# MCU_STM32.net
KiCad netlist of a schematic drawn in Altium Designer
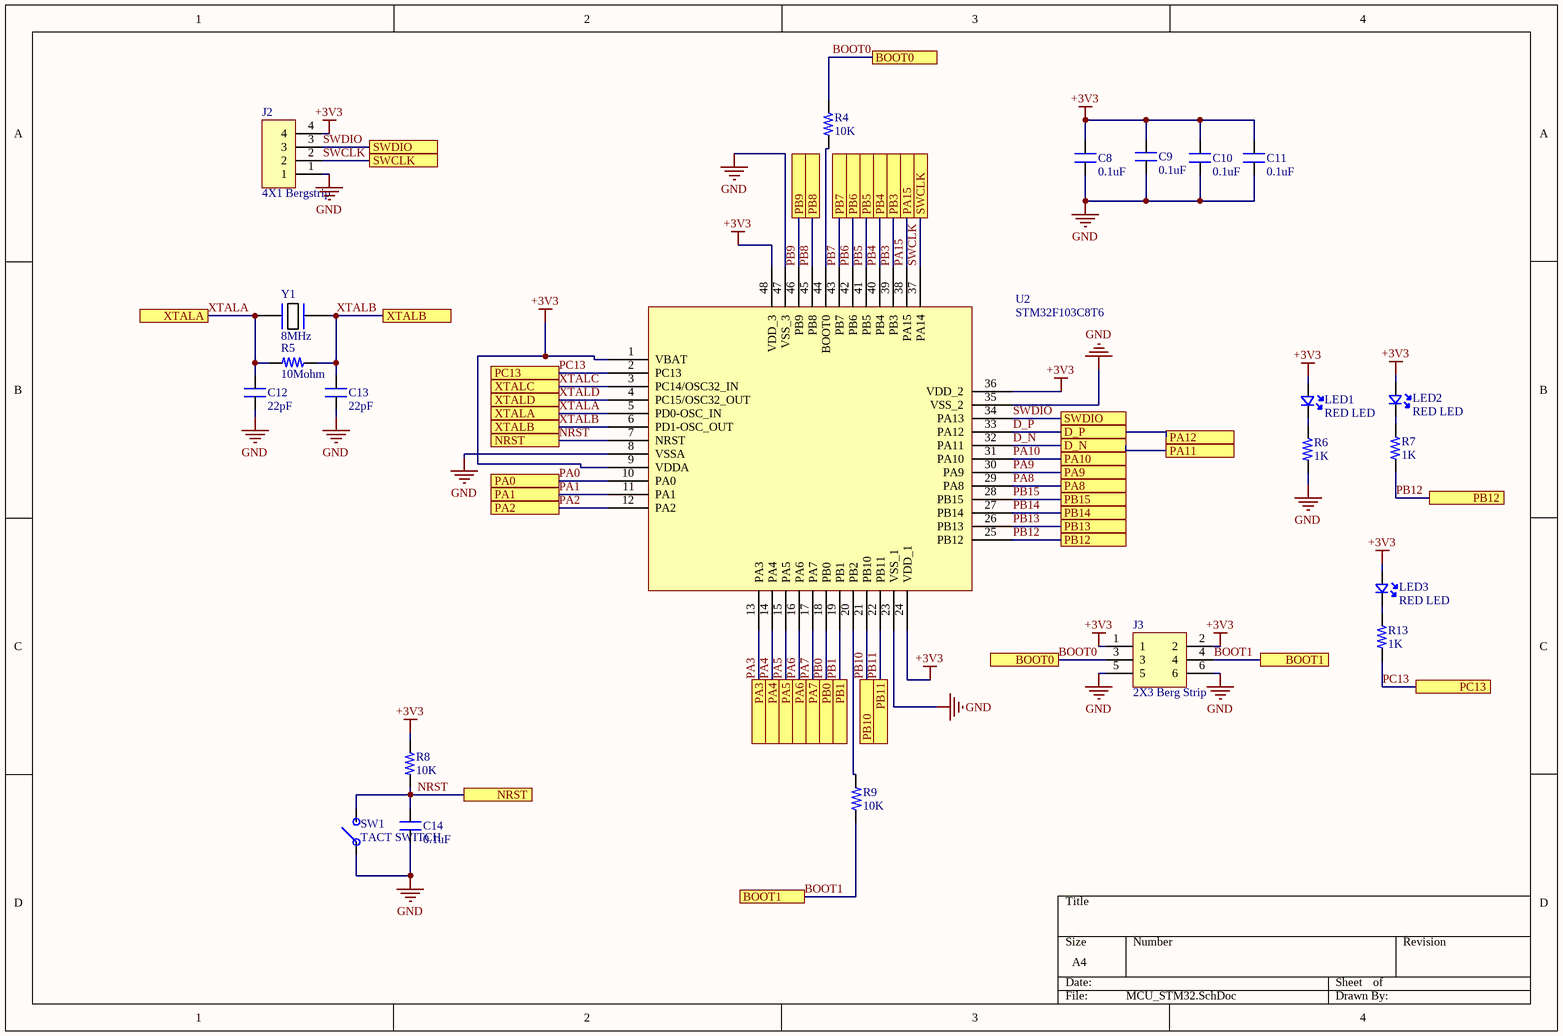
[diagram p0: MCU_STM32.SchDoc]

(export (version "E")
  (design (tool "Eeschema 10.0.6"))
  (components
    (comp (ref "C8")
      (value "0.1uF")
      (footprint "CAP_0805")
      (description "0.1µF ±5% 50V Ceramic Capacitor X7R 0805 (2012 Metric)")
      (fields
        (field (name "MANUFACTURER") "KEMET")
        (field (name "MANUFACTURING PART NUMBER") "C0805C104J5RACTU")
      )
      (libsource (lib "STM_SCH_LIB") (part "CAP_0.1uF-50V-5%-0805"))
    )
    (comp (ref "C9")
      (value "0.1uF")
      (footprint "CAP_0805")
      (description "0.1µF ±5% 50V Ceramic Capacitor X7R 0805 (2012 Metric)")
      (fields
        (field (name "MANUFACTURER") "KEMET")
        (field (name "MANUFACTURING PART NUMBER") "C0805C104J5RACTU")
      )
      (libsource (lib "STM_SCH_LIB") (part "CAP_0.1uF-50V-5%-0805"))
    )
    (comp (ref "C10")
      (value "0.1uF")
      (footprint "CAP_0805")
      (description "0.1µF ±5% 50V Ceramic Capacitor X7R 0805 (2012 Metric)")
      (fields
        (field (name "MANUFACTURER") "KEMET")
        (field (name "MANUFACTURING PART NUMBER") "C0805C104J5RACTU")
      )
      (libsource (lib "STM_SCH_LIB") (part "CAP_0.1uF-50V-5%-0805"))
    )
    (comp (ref "C11")
      (value "0.1uF")
      (footprint "CAP_0805")
      (description "0.1µF ±5% 50V Ceramic Capacitor X7R 0805 (2012 Metric)")
      (fields
        (field (name "MANUFACTURER") "KEMET")
        (field (name "MANUFACTURING PART NUMBER") "C0805C104J5RACTU")
      )
      (libsource (lib "STM_SCH_LIB") (part "CAP_0.1uF-50V-5%-0805"))
    )
    (comp (ref "C12")
      (value "22pF")
      (footprint "CAP_0805")
      (description "22pF ±5% 50V Ceramic Capacitor C0G, NP0 0805 (2012 Metric)")
      (fields
        (field (name "MANUFACTURER") "KEMET")
        (field (name "MANUFACTURER PART NUMBER") "C0805C220J5GACTU")
      )
      (libsource (lib "STM_SCH_LIB") (part "CAP_22pF-50V-5%-0805"))
    )
    (comp (ref "C13")
      (value "22pF")
      (footprint "CAP_0805")
      (description "22pF ±5% 50V Ceramic Capacitor C0G, NP0 0805 (2012 Metric)")
      (fields
        (field (name "MANUFACTURER") "KEMET")
        (field (name "MANUFACTURER PART NUMBER") "C0805C220J5GACTU")
      )
      (libsource (lib "STM_SCH_LIB") (part "CAP_22pF-50V-5%-0805"))
    )
    (comp (ref "C14")
      (value "0.1uF")
      (footprint "CAP_0805")
      (description "0.1µF ±5% 50V Ceramic Capacitor X7R 0805 (2012 Metric)")
      (fields
        (field (name "MANUFACTURER") "KEMET")
        (field (name "MANUFACTURING PART NUMBER") "C0805C104J5RACTU")
      )
      (libsource (lib "STM_SCH_LIB") (part "CAP_0.1uF-50V-5%-0805"))
    )
    (comp (ref "J2")
      (value "4X1 Bergstrip")
      (footprint "CON4_100_40D72_TH_ST_MALE")
      (description "4 pin, 1 row, 2.54mm pitch bergstrip")
      (fields (field (name "MANUFACTURER") "NA"))
      (libsource (lib "STM_SCH_LIB") (part "CON-BS-PLG_4X1-100-TH-ST"))
    )
    (comp (ref "J3")
      (value "2X3 Berg Strip")
      (footprint "CON6_100_59D78_TH_ST_Duplicate")
      (description "6 pin, 2 row, 2.54mm pitch bergstrip")
      (fields (field (name "MANUFACTURER") "NA"))
      (libsource (lib "STM_SCH_LIB") (part "CON-BS-PLG_2X3-100-TH-ST"))
    )
    (comp (ref "LED1")
      (value "RED LED")
      (footprint "LED_0805")
      (description "Red 621nm LED Indication - Discrete 2V 0805 (2012 Metric)")
      (fields
        (field (name "MANUFACTURER") "Lite-On Inc.")
        (field (name "MANUFACTURER PART NUMBER") "LTST-C170EKT")
      )
      (libsource (lib "STM_SCH_LIB") (part "LED-RED_10mA-0805"))
    )
    (comp (ref "LED2")
      (value "RED LED")
      (footprint "LED_0805")
      (description "Red 621nm LED Indication - Discrete 2V 0805 (2012 Metric)")
      (fields
        (field (name "MANUFACTURER") "Lite-On Inc.")
        (field (name "MANUFACTURER PART NUMBER") "LTST-C170EKT")
      )
      (libsource (lib "STM_SCH_LIB") (part "LED-RED_10mA-0805"))
    )
    (comp (ref "LED3")
      (value "RED LED")
      (footprint "LED_0805")
      (description "Red 621nm LED Indication - Discrete 2V 0805 (2012 Metric)")
      (fields
        (field (name "MANUFACTURER") "Lite-On Inc.")
        (field (name "MANUFACTURER PART NUMBER") "LTST-C170EKT")
      )
      (libsource (lib "STM_SCH_LIB") (part "LED-RED_10mA-0805"))
    )
    (comp (ref "R4")
      (value "10K")
      (footprint "RES_0805")
      (description "10 kOhms ±1% 0.125W, 1/8W Chip Resistor 0805 (2012 Metric) Moisture Resistant Thick Film")
      (fields
        (field (name "MANUFACTURER") "Yageo")
        (field (name "MANUFACTURING PART NUMBER") "RC0805FR-0710KL")
      )
      (libsource (lib "STM_SCH_LIB") (part "RES_10K-0.125W-1%-0805"))
    )
    (comp (ref "R5")
      (value "10Mohm")
      (footprint "RES_0805")
      (fields
        (field (name "MANUFACTURER") "Rohm Semiconductor")
        (field (name "MANUFACTURING PART NUMBER") "KTR10EZPF1005")
      )
      (libsource (lib "STM_SCH_LIB") (part "RES_10MOHM-0.125W-1%-0805"))
    )
    (comp (ref "R6")
      (value "1K")
      (footprint "RES_0805")
      (description "1 kOhms ±1% 0.125W, 1/8W Chip Resistor 0805 (2012 Metric) Moisture Resistant Thick Film")
      (fields (field (name "MANUFACTURER") "垈㎵á") (field (name "MANUFACTURER PART NUMBER") "RC0805FR-071KL"))
      (libsource (lib "STM_SCH_LIB") (part "RES_1K-0.125W-1%-0805"))
    )
    (comp (ref "R7")
      (value "1K")
      (footprint "RES_0805")
      (description "1 kOhms ±1% 0.125W, 1/8W Chip Resistor 0805 (2012 Metric) Moisture Resistant Thick Film")
      (fields (field (name "MANUFACTURER") "垈㎵á") (field (name "MANUFACTURER PART NUMBER") "RC0805FR-071KL"))
      (libsource (lib "STM_SCH_LIB") (part "RES_1K-0.125W-1%-0805"))
    )
    (comp (ref "R8")
      (value "10K")
      (footprint "RES_0805")
      (description "10 kOhms ±1% 0.125W, 1/8W Chip Resistor 0805 (2012 Metric) Moisture Resistant Thick Film")
      (fields
        (field (name "MANUFACTURER") "Yageo")
        (field (name "MANUFACTURING PART NUMBER") "RC0805FR-0710KL")
      )
      (libsource (lib "STM_SCH_LIB") (part "RES_10K-0.125W-1%-0805"))
    )
    (comp (ref "R9")
      (value "10K")
      (footprint "RES_0805")
      (description "10 kOhms ±1% 0.125W, 1/8W Chip Resistor 0805 (2012 Metric) Moisture Resistant Thick Film")
      (fields
        (field (name "MANUFACTURER") "Yageo")
        (field (name "MANUFACTURING PART NUMBER") "RC0805FR-0710KL")
      )
      (libsource (lib "STM_SCH_LIB") (part "RES_10K-0.125W-1%-0805"))
    )
    (comp (ref "R13")
      (value "1K")
      (footprint "RES_0805")
      (description "1 kOhms ±1% 0.125W, 1/8W Chip Resistor 0805 (2012 Metric) Moisture Resistant Thick Film")
      (fields (field (name "MANUFACTURER") "垈㎵á") (field (name "MANUFACTURER PART NUMBER") "RC0805FR-071KL"))
      (libsource (lib "STM_SCH_LIB") (part "RES_1K-0.125W-1%-0805"))
    )
    (comp (ref "SW1")
      (value "TACT SWITCH")
      (footprint "SW_342_SMD")
      (description "Tactile Switch SPST-NO Top Actuated Surface Mount")
      (fields (field (name "MANUFACTURER") "C&K") (field (name "MANUFACTURING PART NUMBER") "KSR223GLFG"))
      (libsource (lib "STM_SCH_LIB") (part "SW_KSR223GLFG-SMD"))
    )
    (comp (ref "U2")
      (value "STM32F103C8T6")
      (footprint "LQFP-48_19.6_393_58X11_SMD")
      (description "ARM® Cortex®-M3 STM32F1 Microcontroller IC 32-Bit 72MHz 64KB (64K x 8) FLASH")
      (fields (field (name "MANUFACTURER") "STMicroelectronics"))
      (libsource (lib "STM_SCH_LIB") (part "IC-STM32F103C8T6 _1"))
    )
    (comp (ref "Y1")
      (value "8MHz")
      (footprint "XTAL_314_240X47_SMD")
      (description "Crystals 8MHz 22pF -20C 70C")
      (fields
        (field (name "MANUFACTURER") "IQD Frequency Products")
        (field (name "MANUFACTURING PART NUMBER") "LFXTAL030234Reel")
      )
      (libsource (lib "STM_SCH_LIB") (part "XTAL_8MHZ-LFXTAL030234"))
    )
  )
  (nets
    (net (code "1") (name "+3V3") (class "Default")
      (node (ref "C10") (pin "2") (pinfunction "2_2") (pintype "passive"))
      (node (ref "C11") (pin "2") (pinfunction "2_2") (pintype "passive"))
      (node (ref "C8") (pin "2") (pinfunction "2_2") (pintype "passive"))
      (node (ref "C9") (pin "2") (pinfunction "2_2") (pintype "passive"))
      (node (ref "J2") (pin "4") (pinfunction "4_4") (pintype "passive"))
      (node (ref "J3") (pin "1") (pinfunction "1_1") (pintype "passive"))
      (node (ref "J3") (pin "2") (pinfunction "2_2") (pintype "passive"))
      (node (ref "LED1") (pin "A") (pinfunction "A_A") (pintype "passive"))
      (node (ref "LED2") (pin "A") (pinfunction "A_A") (pintype "passive"))
      (node (ref "LED3") (pin "A") (pinfunction "A_A") (pintype "passive"))
      (node (ref "R8") (pin "2") (pinfunction "2_2") (pintype "passive"))
      (node (ref "U2") (pin "1") (pinfunction "VBAT_1") (pintype "passive"))
      (node (ref "U2") (pin "24") (pinfunction "VDD_1_24") (pintype "passive"))
      (node (ref "U2") (pin "36") (pinfunction "VDD_2_36") (pintype "passive"))
      (node (ref "U2") (pin "48") (pinfunction "VDD_3_48") (pintype "passive"))
      (node (ref "U2") (pin "9") (pinfunction "VDDA_9") (pintype "passive"))
    )
    (net (code "2") (name "/BOOT0") (class "Default")
      (node (ref "J3") (pin "3") (pinfunction "3_3") (pintype "passive"))
      (node (ref "R4") (pin "2") (pinfunction "2_2") (pintype "passive"))
    )
    (net (code "3") (name "/BOOT1") (class "Default")
      (node (ref "J3") (pin "4") (pinfunction "4_4") (pintype "passive"))
      (node (ref "R9") (pin "2") (pinfunction "2_2") (pintype "passive"))
    )
    (net (code "4") (name "/D_N") (class "Default")
      (node (ref "U2") (pin "32") (pinfunction "PA11_32") (pintype "passive"))
    )
    (net (code "5") (name "/D_P") (class "Default")
      (node (ref "U2") (pin "33") (pinfunction "PA12_33") (pintype "passive"))
    )
    (net (code "6") (name "/NRST") (class "Default")
      (node (ref "C14") (pin "2") (pinfunction "2_2") (pintype "passive"))
      (node (ref "R8") (pin "1") (pinfunction "1_1") (pintype "passive"))
      (node (ref "SW1") (pin "2") (pinfunction "2_2") (pintype "passive"))
      (node (ref "U2") (pin "7") (pinfunction "NRST_7") (pintype "passive"))
    )
    (net (code "7") (name "/PA0") (class "Default")
      (node (ref "U2") (pin "10") (pinfunction "PA0_10") (pintype "passive"))
    )
    (net (code "8") (name "/PA1") (class "Default")
      (node (ref "U2") (pin "11") (pinfunction "PA1_11") (pintype "passive"))
    )
    (net (code "9") (name "/PA2") (class "Default")
      (node (ref "U2") (pin "12") (pinfunction "PA2_12") (pintype "passive"))
    )
    (net (code "10") (name "/PA3") (class "Default")
      (node (ref "U2") (pin "13") (pinfunction "PA3_13") (pintype "passive"))
    )
    (net (code "11") (name "/PA4") (class "Default")
      (node (ref "U2") (pin "14") (pinfunction "PA4_14") (pintype "passive"))
    )
    (net (code "12") (name "/PA5") (class "Default")
      (node (ref "U2") (pin "15") (pinfunction "PA5_15") (pintype "passive"))
    )
    (net (code "13") (name "/PA6") (class "Default")
      (node (ref "U2") (pin "16") (pinfunction "PA6_16") (pintype "passive"))
    )
    (net (code "14") (name "/PA7") (class "Default")
      (node (ref "U2") (pin "17") (pinfunction "PA7_17") (pintype "passive"))
    )
    (net (code "15") (name "/PA8") (class "Default")
      (node (ref "U2") (pin "29") (pinfunction "PA8_29") (pintype "passive"))
    )
    (net (code "16") (name "/PA9") (class "Default")
      (node (ref "U2") (pin "30") (pinfunction "PA9_30") (pintype "passive"))
    )
    (net (code "17") (name "/PA10") (class "Default")
      (node (ref "U2") (pin "31") (pinfunction "PA10_31") (pintype "passive"))
    )
    (net (code "18") (name "/PA15") (class "Default")
      (node (ref "U2") (pin "38") (pinfunction "PA15_38") (pintype "passive"))
    )
    (net (code "19") (name "/PB0") (class "Default")
      (node (ref "U2") (pin "18") (pinfunction "PB0_18") (pintype "passive"))
    )
    (net (code "20") (name "/PB1") (class "Default")
      (node (ref "U2") (pin "19") (pinfunction "PB1_19") (pintype "passive"))
    )
    (net (code "21") (name "/PB3") (class "Default")
      (node (ref "U2") (pin "39") (pinfunction "PB3_39") (pintype "passive"))
    )
    (net (code "22") (name "/PB4") (class "Default")
      (node (ref "U2") (pin "40") (pinfunction "PB4_40") (pintype "passive"))
    )
    (net (code "23") (name "/PB5") (class "Default")
      (node (ref "U2") (pin "41") (pinfunction "PB5_41") (pintype "passive"))
    )
    (net (code "24") (name "/PB6") (class "Default")
      (node (ref "U2") (pin "42") (pinfunction "PB6_42") (pintype "passive"))
    )
    (net (code "25") (name "/PB7") (class "Default")
      (node (ref "U2") (pin "43") (pinfunction "PB7_43") (pintype "passive"))
    )
    (net (code "26") (name "/PB8") (class "Default")
      (node (ref "U2") (pin "45") (pinfunction "PB8_45") (pintype "passive"))
    )
    (net (code "27") (name "/PB9") (class "Default")
      (node (ref "U2") (pin "46") (pinfunction "PB9_46") (pintype "passive"))
    )
    (net (code "28") (name "/PB10") (class "Default")
      (node (ref "U2") (pin "21") (pinfunction "PB10_21") (pintype "passive"))
    )
    (net (code "29") (name "/PB11") (class "Default")
      (node (ref "U2") (pin "22") (pinfunction "PB11_22") (pintype "passive"))
    )
    (net (code "30") (name "/PB12") (class "Default")
      (node (ref "R7") (pin "1") (pinfunction "1_1") (pintype "passive"))
      (node (ref "U2") (pin "25") (pinfunction "PB12_25") (pintype "passive"))
    )
    (net (code "31") (name "/PB13") (class "Default")
      (node (ref "U2") (pin "26") (pinfunction "PB13_26") (pintype "passive"))
    )
    (net (code "32") (name "/PB14") (class "Default")
      (node (ref "U2") (pin "27") (pinfunction "PB14_27") (pintype "passive"))
    )
    (net (code "33") (name "/PB15") (class "Default")
      (node (ref "U2") (pin "28") (pinfunction "PB15_28") (pintype "passive"))
    )
    (net (code "34") (name "/PC13") (class "Default")
      (node (ref "R13") (pin "1") (pinfunction "1_1") (pintype "passive"))
      (node (ref "U2") (pin "2") (pinfunction "PC13_2") (pintype "passive"))
    )
    (net (code "35") (name "/SWCLK") (class "Default")
      (node (ref "J2") (pin "2") (pinfunction "2_2") (pintype "passive"))
      (node (ref "U2") (pin "37") (pinfunction "PA14_37") (pintype "passive"))
    )
    (net (code "36") (name "/SWDIO") (class "Default")
      (node (ref "J2") (pin "3") (pinfunction "3_3") (pintype "passive"))
      (node (ref "U2") (pin "34") (pinfunction "PA13_34") (pintype "passive"))
    )
    (net (code "37") (name "/XTALA") (class "Default")
      (node (ref "C12") (pin "2") (pinfunction "2_2") (pintype "passive"))
      (node (ref "R5") (pin "1") (pinfunction "1_1") (pintype "passive"))
      (node (ref "U2") (pin "5") (pinfunction "PD0-OSC_IN_5") (pintype "passive"))
      (node (ref "Y1") (pin "1") (pinfunction "1_1") (pintype "passive"))
    )
    (net (code "38") (name "/XTALB") (class "Default")
      (node (ref "C13") (pin "2") (pinfunction "2_2") (pintype "passive"))
      (node (ref "R5") (pin "2") (pinfunction "2_2") (pintype "passive"))
      (node (ref "U2") (pin "6") (pinfunction "PD1-OSC_OUT_6") (pintype "passive"))
      (node (ref "Y1") (pin "2") (pinfunction "2_2") (pintype "passive"))
    )
    (net (code "39") (name "/XTALC") (class "Default")
      (node (ref "U2") (pin "3") (pinfunction "PC14/OSC32_IN_3") (pintype "passive"))
    )
    (net (code "40") (name "/XTALD") (class "Default")
      (node (ref "U2") (pin "4") (pinfunction "PC15/OSC32_OUT_4") (pintype "passive"))
    )
    (net (code "41") (name "GND") (class "Default")
      (node (ref "C10") (pin "1") (pinfunction "1_1") (pintype "passive"))
      (node (ref "C11") (pin "1") (pinfunction "1_1") (pintype "passive"))
      (node (ref "C12") (pin "1") (pinfunction "1_1") (pintype "passive"))
      (node (ref "C13") (pin "1") (pinfunction "1_1") (pintype "passive"))
      (node (ref "C14") (pin "1") (pinfunction "1_1") (pintype "passive"))
      (node (ref "C8") (pin "1") (pinfunction "1_1") (pintype "passive"))
      (node (ref "C9") (pin "1") (pinfunction "1_1") (pintype "passive"))
      (node (ref "J2") (pin "1") (pinfunction "1_1") (pintype "passive"))
      (node (ref "J3") (pin "5") (pinfunction "5_5") (pintype "passive"))
      (node (ref "J3") (pin "6") (pinfunction "6_6") (pintype "passive"))
      (node (ref "R6") (pin "1") (pinfunction "1_1") (pintype "passive"))
      (node (ref "SW1") (pin "1") (pinfunction "1_1") (pintype "passive"))
      (node (ref "U2") (pin "23") (pinfunction "VSS_1_23") (pintype "passive"))
      (node (ref "U2") (pin "35") (pinfunction "VSS_2_35") (pintype "passive"))
      (node (ref "U2") (pin "47") (pinfunction "VSS_3_47") (pintype "passive"))
      (node (ref "U2") (pin "8") (pinfunction "VSSA_8") (pintype "passive"))
    )
    (net (code "42") (name "Net-(LED1-PadK)") (class "Default")
      (node (ref "LED1") (pin "K") (pinfunction "K_K") (pintype "passive"))
      (node (ref "R6") (pin "2") (pinfunction "2_2") (pintype "passive"))
    )
    (net (code "43") (name "Net-(LED2-PadK)") (class "Default")
      (node (ref "LED2") (pin "K") (pinfunction "K_K") (pintype "passive"))
      (node (ref "R7") (pin "2") (pinfunction "2_2") (pintype "passive"))
    )
    (net (code "44") (name "Net-(LED3-PadK)") (class "Default")
      (node (ref "LED3") (pin "K") (pinfunction "K_K") (pintype "passive"))
      (node (ref "R13") (pin "2") (pinfunction "2_2") (pintype "passive"))
    )
    (net (code "45") (name "Net-(U2-BOOT0)") (class "Default")
      (node (ref "R4") (pin "1") (pinfunction "1_1") (pintype "passive"))
      (node (ref "U2") (pin "44") (pinfunction "BOOT0_44") (pintype "passive"))
    )
    (net (code "46") (name "Net-(U2-PB2)") (class "Default")
      (node (ref "R9") (pin "1") (pinfunction "1_1") (pintype "passive"))
      (node (ref "U2") (pin "20") (pinfunction "PB2_20") (pintype "passive"))
    )
  )
)
